# Battery_pack.net
KiCad netlist of a schematic drawn in EAGLE
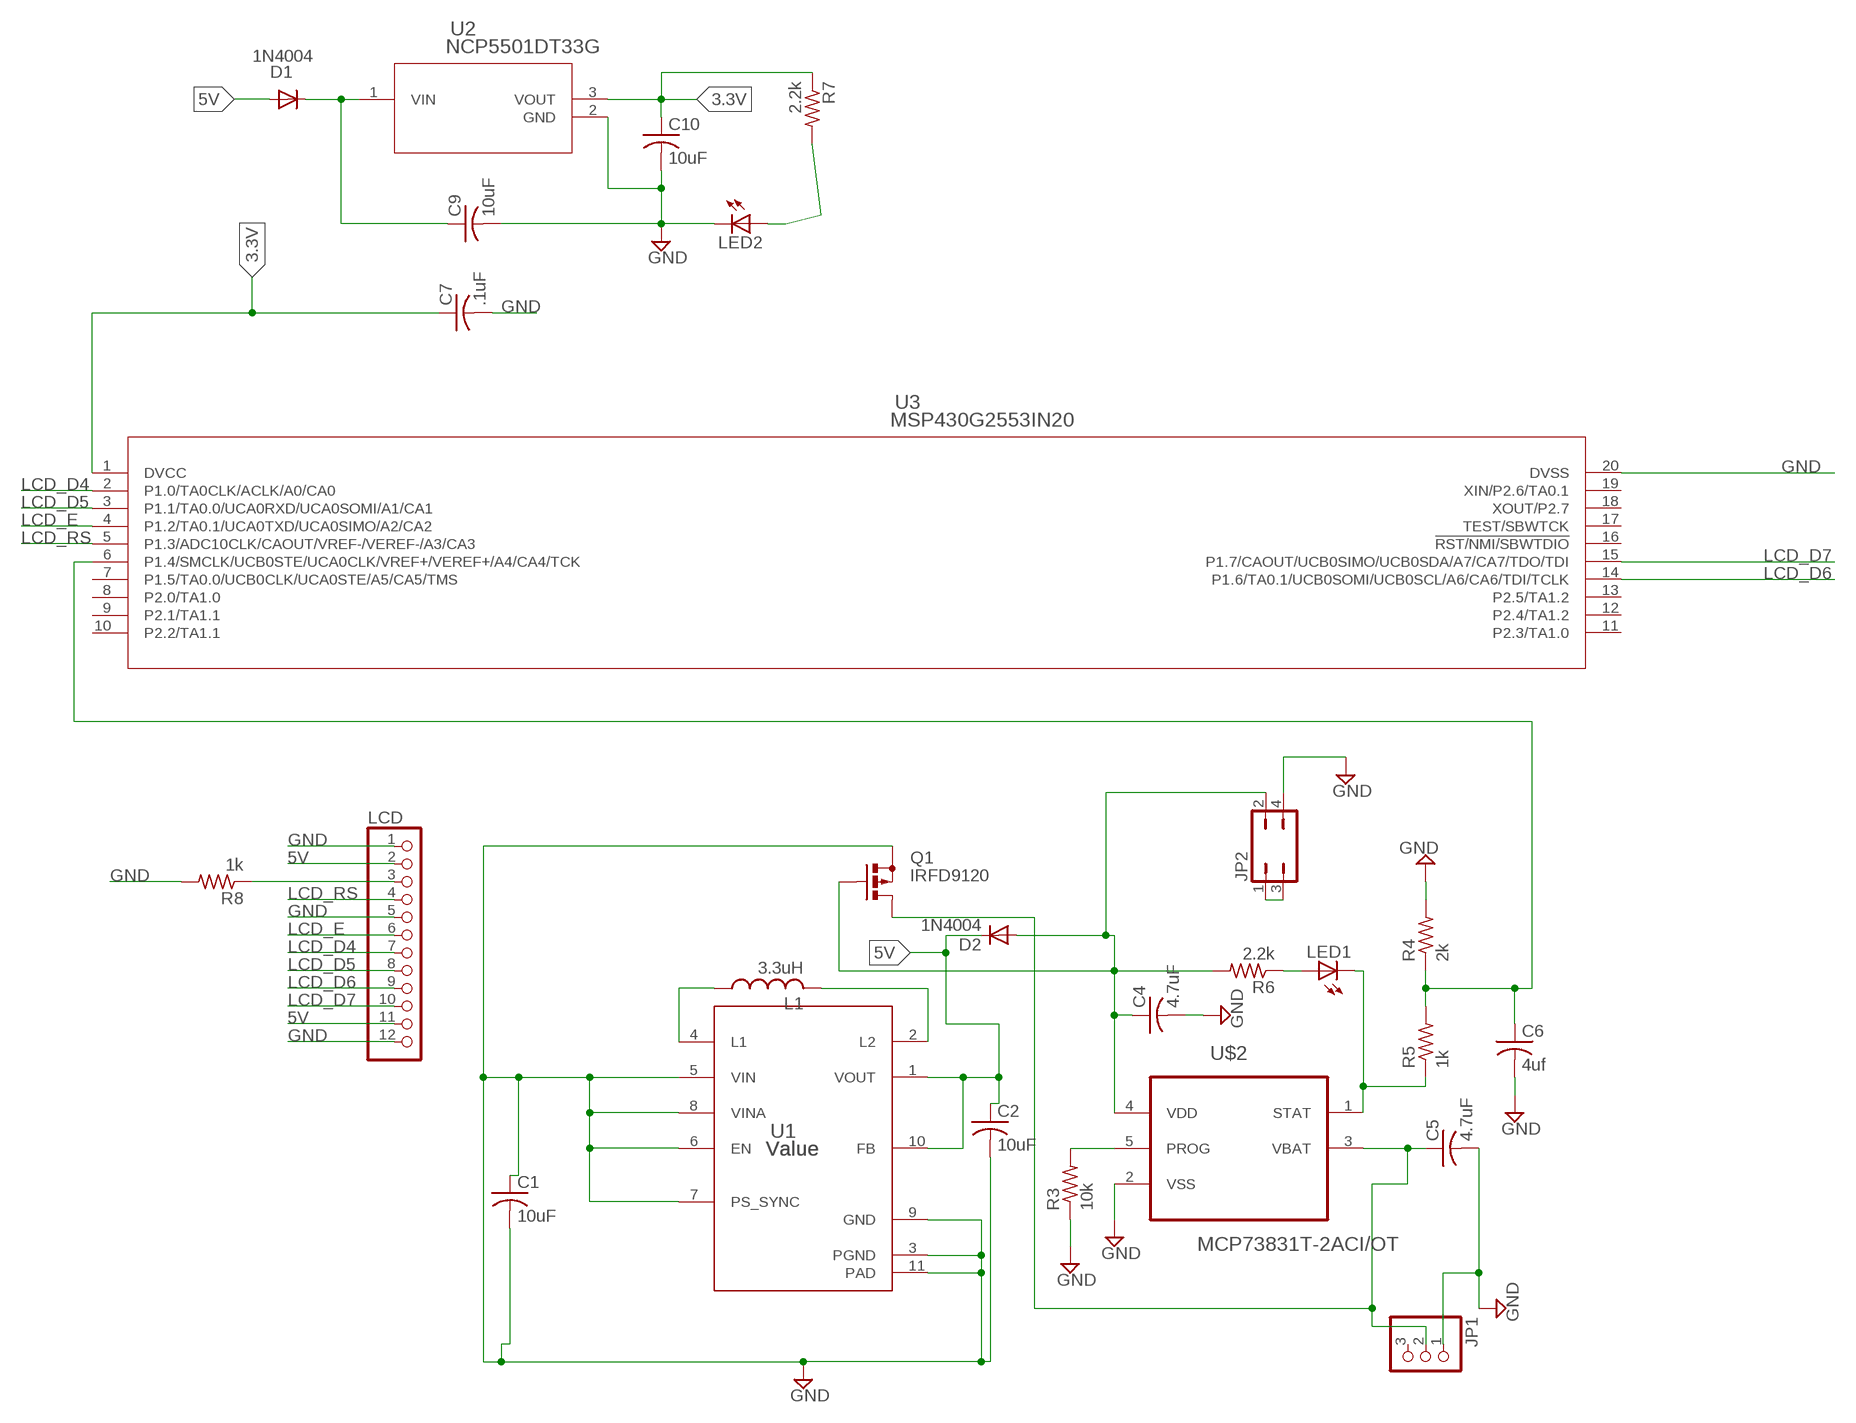
[diagram p0: schematic, sheet 1]

(export (version "E")
  (design (tool "Eeschema 10.0.6"))
  (components
    (comp (ref "C1")
      (value "10uF")
      (footprint "eagle-import:C150-064X183")
      (libsource (lib "eagle-import") (part "C-US150-064X183"))
    )
    (comp (ref "C2")
      (value "10uF")
      (footprint "eagle-import:C150-064X183")
      (libsource (lib "eagle-import") (part "C-US150-064X183"))
    )
    (comp (ref "C4")
      (value "4.7uF")
      (footprint "eagle-import:C150-064X183")
      (libsource (lib "eagle-import") (part "C-US150-064X183"))
    )
    (comp (ref "C5")
      (value "4.7uF")
      (footprint "eagle-import:C150-064X183")
      (libsource (lib "eagle-import") (part "C-US150-064X183"))
    )
    (comp (ref "C6")
      (value "4uf")
      (footprint "eagle-import:C150-064X183")
      (libsource (lib "eagle-import") (part "C-US150-064X183"))
    )
    (comp (ref "C7")
      (value ".1uF")
      (footprint "eagle-import:C150-064X183")
      (libsource (lib "eagle-import") (part "C-US150-064X183"))
    )
    (comp (ref "C9")
      (value "10uF")
      (footprint "eagle-import:C150-064X183")
      (libsource (lib "eagle-import") (part "C-US150-064X183"))
    )
    (comp (ref "C10")
      (value "10uF")
      (footprint "eagle-import:C150-064X183")
      (libsource (lib "eagle-import") (part "C-US150-064X183"))
    )
    (comp (ref "D1")
      (value "1N4004")
      (footprint "eagle-import:DO41-10")
      (libsource (lib "eagle-import") (part "1N4004"))
    )
    (comp (ref "D2")
      (value "1N4004")
      (footprint "eagle-import:DO41-10")
      (libsource (lib "eagle-import") (part "1N4004"))
    )
    (comp (ref "JP1")
      (value "PINHD-1X3")
      (footprint "eagle-import:1X03")
      (libsource (lib "eagle-import") (part "PINHD-1X3"))
    )
    (comp (ref "JP2")
      (value "JP2Q")
      (footprint "eagle-import:JP2Q")
      (libsource (lib "eagle-import") (part "JP2Q"))
    )
    (comp (ref "L1")
      (value "3.3uH")
      (footprint "eagle-import:0207_15")
      (libsource (lib "eagle-import") (part "L-US0207/15"))
    )
    (comp (ref "LCD")
      (value "PINHD-1X12")
      (footprint "eagle-import:1X12")
      (libsource (lib "eagle-import") (part "PINHD-1X12"))
    )
    (comp (ref "LED1")
      (value "LEDB155")
      (footprint "eagle-import:Q62902-B155")
      (libsource (lib "eagle-import") (part "LEDB155"))
    )
    (comp (ref "LED2")
      (value "LEDB155")
      (footprint "eagle-import:Q62902-B155")
      (libsource (lib "eagle-import") (part "LEDB155"))
    )
    (comp (ref "Q1")
      (value "IRFD9120")
      (footprint "eagle-import:C370-01")
      (libsource (lib "eagle-import") (part "IRFD9120"))
    )
    (comp (ref "R3")
      (value "10k")
      (footprint "eagle-import:0207_15")
      (libsource (lib "eagle-import") (part "R-US_0207/15"))
    )
    (comp (ref "R4")
      (value "2k")
      (footprint "eagle-import:0207_15")
      (libsource (lib "eagle-import") (part "R-US_0207/15"))
    )
    (comp (ref "R5")
      (value "1k")
      (footprint "eagle-import:0207_15")
      (libsource (lib "eagle-import") (part "R-US_0207/15"))
    )
    (comp (ref "R6")
      (value "2.2k")
      (footprint "eagle-import:0207_15")
      (libsource (lib "eagle-import") (part "R-US_0207/15"))
    )
    (comp (ref "R7")
      (value "2.2k")
      (footprint "eagle-import:0207_15")
      (libsource (lib "eagle-import") (part "R-US_0207/15"))
    )
    (comp (ref "R8")
      (value "1k")
      (footprint "eagle-import:0207_15")
      (libsource (lib "eagle-import") (part "R-US_0207/15"))
    )
    (comp (ref "U$2")
      (value "MCP73831T-2ACI/OT")
      (footprint "eagle-import:SOT95P280X145-5N")
      (fields (field (name "MF") "Microchip"))
      (libsource (lib "eagle-import") (part "MCP73831T-2ACI/OT"))
    )
    (comp (ref "U1")
      (value "Value")
      (footprint "eagle-import:DRC0010J")
      (fields
        (field (name "ALTERNATE_PARTNUMBER") "TPS63002DRCT")
        (field (name "MANUFACTURER") "Texas Instruments")
        (field (name "PARTNUMBER") "TPS63002DRCR")
      )
      (libsource (lib "eagle-import") (part "TPS63002DRCR"))
    )
    (comp (ref "U2")
      (value "NCP5501DT33G")
      (footprint "eagle-import:DPAK-3_ONS")
      (fields (field (name "COPYRIGHT") "Copyright (C) 2016 Accelerated Designs. All rights reserved"))
      (libsource (lib "eagle-import") (part "NCP5501DT33G"))
    )
    (comp (ref "U3")
      (value "MSP430G2553IN20")
      (footprint "eagle-import:N20_TEX")
      (libsource (lib "eagle-import") (part "MSP430G2553IN20"))
    )
  )
  (nets
    (net (code "1") (name "/LCD_D4") (class "Default")
      (node (ref "LCD") (pin "7") (pinfunction "7_7") (pintype "passive"))
      (node (ref "U3") (pin "2") (pinfunction "P1.0/TA0CLK/ACLK/A0/CA0_2") (pintype "bidirectional"))
    )
    (net (code "2") (name "/LCD_D5") (class "Default")
      (node (ref "LCD") (pin "8") (pinfunction "8_8") (pintype "passive"))
      (node (ref "U3") (pin "3") (pinfunction "P1.1/TA0.0/UCA0RXD/UCA0SOMI/A1/CA1_3") (pintype "bidirectional"))
    )
    (net (code "3") (name "/LCD_D6") (class "Default")
      (node (ref "LCD") (pin "9") (pinfunction "9_9") (pintype "passive"))
      (node (ref "U3") (pin "14") (pinfunction "P1.6/TA0.1/UCB0SOMI/UCB0SCL/A6/CA6/TDI/TCLK_14") (pintype "bidirectional"))
    )
    (net (code "4") (name "/LCD_D7") (class "Default")
      (node (ref "LCD") (pin "10") (pinfunction "10_10") (pintype "passive"))
      (node (ref "U3") (pin "15") (pinfunction "P1.7/CAOUT/UCB0SIMO/UCB0SDA/A7/CA7/TDO/TDI_15") (pintype "bidirectional"))
    )
    (net (code "5") (name "/LCD_E") (class "Default")
      (node (ref "LCD") (pin "6") (pinfunction "6_6") (pintype "passive"))
      (node (ref "U3") (pin "4") (pinfunction "P1.2/TA0.1/UCA0TXD/UCA0SIMO/A2/CA2_4") (pintype "bidirectional"))
    )
    (net (code "6") (name "/LCD_RS") (class "Default")
      (node (ref "LCD") (pin "4") (pinfunction "4_4") (pintype "passive"))
      (node (ref "U3") (pin "5") (pinfunction "P1.3/ADC10CLK/CAOUT/VREF-/VEREF-/A3/CA3_5") (pintype "bidirectional"))
    )
    (net (code "7") (name "3.3V") (class "Default")
      (node (ref "C10") (pin "1") (pinfunction "1_1") (pintype "passive"))
      (node (ref "C7") (pin "1") (pinfunction "1_1") (pintype "passive"))
      (node (ref "R7") (pin "1") (pinfunction "1_1") (pintype "passive"))
      (node (ref "U2") (pin "3") (pinfunction "VOUT_3") (pintype "output"))
      (node (ref "U3") (pin "1") (pinfunction "DVCC_1") (pintype "power_in"))
    )
    (net (code "8") (name "5V") (class "Default")
      (node (ref "C2") (pin "1") (pinfunction "1_1") (pintype "passive"))
      (node (ref "D1") (pin "A") (pinfunction "A_A") (pintype "passive"))
      (node (ref "D2") (pin "C") (pinfunction "C_C") (pintype "passive"))
      (node (ref "LCD") (pin "11") (pinfunction "11_11") (pintype "passive"))
      (node (ref "LCD") (pin "2") (pinfunction "2_2") (pintype "passive"))
      (node (ref "U1") (pin "1") (pinfunction "VOUT_1") (pintype "power_in"))
      (node (ref "U1") (pin "10") (pinfunction "FB_10") (pintype "input"))
    )
    (net (code "9") (name "GND") (class "Default")
      (node (ref "C1") (pin "1") (pinfunction "1_1") (pintype "passive"))
      (node (ref "C1") (pin "2") (pinfunction "2_2") (pintype "passive"))
      (node (ref "C10") (pin "2") (pinfunction "2_2") (pintype "passive"))
      (node (ref "C2") (pin "2") (pinfunction "2_2") (pintype "passive"))
      (node (ref "C4") (pin "2") (pinfunction "2_2") (pintype "passive"))
      (node (ref "C5") (pin "2") (pinfunction "2_2") (pintype "passive"))
      (node (ref "C6") (pin "2") (pinfunction "2_2") (pintype "passive"))
      (node (ref "C7") (pin "2") (pinfunction "2_2") (pintype "passive"))
      (node (ref "C9") (pin "2") (pinfunction "2_2") (pintype "passive"))
      (node (ref "JP1") (pin "1") (pinfunction "1_1") (pintype "passive"))
      (node (ref "JP2") (pin "4") (pinfunction "4_4") (pintype "passive"))
      (node (ref "LCD") (pin "1") (pinfunction "1_1") (pintype "passive"))
      (node (ref "LCD") (pin "12") (pinfunction "12_12") (pintype "passive"))
      (node (ref "LCD") (pin "5") (pinfunction "5_5") (pintype "passive"))
      (node (ref "LED2") (pin "K") (pinfunction "C_K") (pintype "passive"))
      (node (ref "Q1") (pin "S") (pinfunction "S_S") (pintype "passive"))
      (node (ref "R3") (pin "1") (pinfunction "1_1") (pintype "passive"))
      (node (ref "R4") (pin "2") (pinfunction "2_2") (pintype "passive"))
      (node (ref "R8") (pin "2") (pinfunction "2_2") (pintype "passive"))
      (node (ref "U$2") (pin "2") (pinfunction "VSS_2") (pintype "power_in"))
      (node (ref "U1") (pin "11") (pinfunction "PAD_11") (pintype "power_in"))
      (node (ref "U1") (pin "3") (pinfunction "PGND_3") (pintype "power_in"))
      (node (ref "U1") (pin "5") (pinfunction "VIN_5") (pintype "power_in"))
      (node (ref "U1") (pin "6") (pinfunction "EN_6") (pintype "input"))
      (node (ref "U1") (pin "7") (pinfunction "PS_SYNC_7") (pintype "input"))
      (node (ref "U1") (pin "8") (pinfunction "VINA_8") (pintype "power_in"))
      (node (ref "U1") (pin "9") (pinfunction "GND_9") (pintype "power_in"))
      (node (ref "U2") (pin "2") (pinfunction "GND_2") (pintype "power_in"))
      (node (ref "U3") (pin "20") (pinfunction "DVSS_20") (pintype "power_in"))
    )
    (net (code "10") (name "Net-(JP2-Pad1)") (class "Default")
      (node (ref "JP2") (pin "1") (pinfunction "1_1") (pintype "passive"))
      (node (ref "JP2") (pin "3") (pinfunction "3_3") (pintype "passive"))
    )
    (net (code "11") (name "Net-(LCD-Pad3)") (class "Default")
      (node (ref "LCD") (pin "3") (pinfunction "3_3") (pintype "passive"))
      (node (ref "R8") (pin "1") (pinfunction "1_1") (pintype "passive"))
    )
    (net (code "12") (name "Net-(LED1-C)") (class "Default")
      (node (ref "LED1") (pin "K") (pinfunction "C_K") (pintype "passive"))
      (node (ref "R5") (pin "1") (pinfunction "1_1") (pintype "passive"))
      (node (ref "U$2") (pin "1") (pinfunction "STAT_1") (pintype "output"))
    )
    (net (code "13") (name "Net-(LED1-PadA)") (class "Default")
      (node (ref "LED1") (pin "A") (pinfunction "A_A") (pintype "passive"))
      (node (ref "R6") (pin "1") (pinfunction "1_1") (pintype "passive"))
    )
    (net (code "14") (name "Net-(LED2-PadA)") (class "Default")
      (node (ref "LED2") (pin "A") (pinfunction "A_A") (pintype "passive"))
      (node (ref "R7") (pin "2") (pinfunction "2_2") (pintype "passive"))
    )
    (net (code "15") (name "Net-(U$2-PROG)") (class "Default")
      (node (ref "R3") (pin "2") (pinfunction "2_2") (pintype "passive"))
      (node (ref "U$2") (pin "5") (pinfunction "PROG_5") (pintype "input"))
    )
    (net (code "16") (name "Net-(U$2-VBAT)") (class "Default")
      (node (ref "C5") (pin "1") (pinfunction "1_1") (pintype "passive"))
      (node (ref "JP1") (pin "2") (pinfunction "2_2") (pintype "passive"))
      (node (ref "Q1") (pin "D") (pinfunction "D_D") (pintype "passive"))
      (node (ref "Q1") (pin "D1") (pinfunction "D_D1") (pintype "passive"))
      (node (ref "U$2") (pin "3") (pinfunction "VBAT_3") (pintype "output"))
    )
    (net (code "17") (name "Net-(U$2-VDD)") (class "Default")
      (node (ref "C4") (pin "1") (pinfunction "1_1") (pintype "passive"))
      (node (ref "D2") (pin "A") (pinfunction "A_A") (pintype "passive"))
      (node (ref "JP2") (pin "2") (pinfunction "2_2") (pintype "passive"))
      (node (ref "Q1") (pin "G") (pinfunction "G_G") (pintype "passive"))
      (node (ref "R6") (pin "2") (pinfunction "2_2") (pintype "passive"))
      (node (ref "U$2") (pin "4") (pinfunction "VDD_4") (pintype "power_in"))
    )
    (net (code "18") (name "Net-(U1-L1)") (class "Default")
      (node (ref "L1") (pin "1") (pinfunction "1_1") (pintype "passive"))
      (node (ref "U1") (pin "4") (pinfunction "L1_4") (pintype "passive"))
    )
    (net (code "19") (name "Net-(U1-L2)") (class "Default")
      (node (ref "L1") (pin "2") (pinfunction "2_2") (pintype "passive"))
      (node (ref "U1") (pin "2") (pinfunction "L2_2") (pintype "passive"))
    )
    (net (code "20") (name "Net-(U2-VIN)") (class "Default")
      (node (ref "C9") (pin "1") (pinfunction "1_1") (pintype "passive"))
      (node (ref "D1") (pin "C") (pinfunction "C_C") (pintype "passive"))
      (node (ref "U2") (pin "1") (pinfunction "VIN_1") (pintype "input"))
    )
    (net (code "21") (name "Net-(U3-P1.4{slash}SMCLK{slash}UCB0STE{slash}UCA0CLK{slash}VREF+{slash}VEREF+{slash}A4{slash}CA4{slash}TCK)") (class "Default")
      (node (ref "C6") (pin "1") (pinfunction "1_1") (pintype "passive"))
      (node (ref "R4") (pin "1") (pinfunction "1_1") (pintype "passive"))
      (node (ref "R5") (pin "2") (pinfunction "2_2") (pintype "passive"))
      (node (ref "U3") (pin "6") (pinfunction "P1.4/SMCLK/UCB0STE/UCA0CLK/VREF+/VEREF+/A4/CA4/TCK_6") (pintype "bidirectional"))
    )
    (net (code "22") (name "unconnected-(JP1-Pad3)") (class "Default")
      (node (ref "JP1") (pin "3") (pinfunction "3_3") (pintype "passive"))
    )
    (net (code "23") (name "unconnected-(U3-P1.5{slash}TA0.0{slash}UCB0CLK{slash}UCA0STE{slash}A5{slash}CA5{slash}TMS-Pad7)") (class "Default")
      (node (ref "U3") (pin "7") (pinfunction "P1.5/TA0.0/UCB0CLK/UCA0STE/A5/CA5/TMS_7") (pintype "bidirectional"))
    )
    (net (code "24") (name "unconnected-(U3-P2.0{slash}TA1.0-Pad8)") (class "Default")
      (node (ref "U3") (pin "8") (pinfunction "P2.0/TA1.0_8") (pintype "bidirectional"))
    )
    (net (code "25") (name "unconnected-(U3-P2.1{slash}TA1.1-Pad9)") (class "Default")
      (node (ref "U3") (pin "9") (pinfunction "P2.1/TA1.1_9") (pintype "bidirectional"))
    )
    (net (code "26") (name "unconnected-(U3-P2.2{slash}TA1.1-Pad10)") (class "Default")
      (node (ref "U3") (pin "10") (pinfunction "P2.2/TA1.1_10") (pintype "bidirectional"))
    )
    (net (code "27") (name "unconnected-(U3-P2.3{slash}TA1.0-Pad11)") (class "Default")
      (node (ref "U3") (pin "11") (pinfunction "P2.3/TA1.0_11") (pintype "bidirectional"))
    )
    (net (code "28") (name "unconnected-(U3-P2.4{slash}TA1.2-Pad12)") (class "Default")
      (node (ref "U3") (pin "12") (pinfunction "P2.4/TA1.2_12") (pintype "bidirectional"))
    )
    (net (code "29") (name "unconnected-(U3-P2.5{slash}TA1.2-Pad13)") (class "Default")
      (node (ref "U3") (pin "13") (pinfunction "P2.5/TA1.2_13") (pintype "bidirectional"))
    )
    (net (code "30") (name "unconnected-(U3-TEST{slash}SBWTCK-Pad17)") (class "Default")
      (node (ref "U3") (pin "17") (pinfunction "TEST/SBWTCK_17") (pintype "bidirectional"))
    )
    (net (code "31") (name "unconnected-(U3-XIN{slash}P2.6{slash}TA0.1-Pad19)") (class "Default")
      (node (ref "U3") (pin "19") (pinfunction "XIN/P2.6/TA0.1_19") (pintype "bidirectional"))
    )
    (net (code "32") (name "unconnected-(U3-XOUT{slash}P2.7-Pad18)") (class "Default")
      (node (ref "U3") (pin "18") (pinfunction "XOUT/P2.7_18") (pintype "bidirectional"))
    )
    (net (code "33") (name "unconnected-(U3-~{RST{slash}NMI{slash}SBWTDIO}-Pad16)") (class "Default")
      (node (ref "U3") (pin "16") (pinfunction "~{RST/NMI/SBWTDIO}_16") (pintype "bidirectional"))
    )
  )
)
